# VCO.net
KiCad netlist of a schematic drawn in Altium Designer
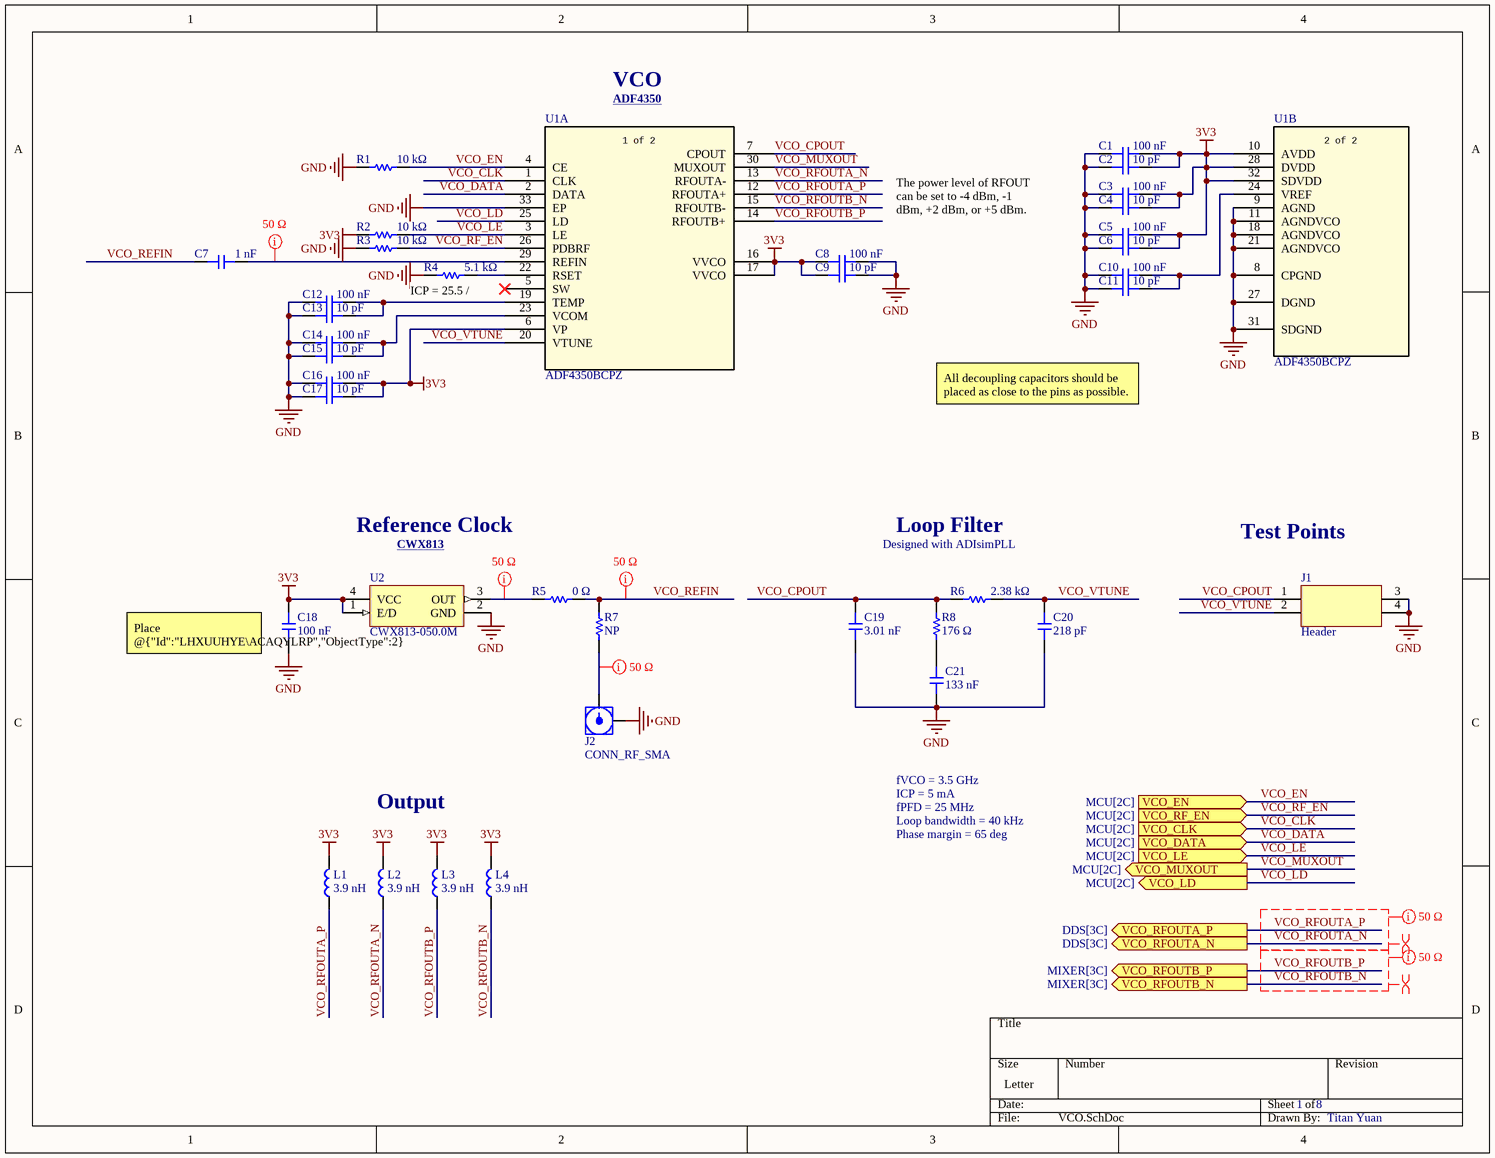
[diagram p0: VCO.SchDoc]

(export (version "E")
  (design (tool "Eeschema 10.0.6"))
  (components
    (comp (ref "C1")
      (value "100 nF")
      (footprint "CAP_0402")
      (description "Ceramic Capacitor, Ceramic, 50V, 10% +Tol, 10% -Tol, X7R, 15% TC, 0.1uF, Surface Mount, 0402")
      (fields
        (field (name "MANUFACTURER") "Yageo")
        (field (name "MANUFACTURER PART NUMBER") "CC0402KPX7R9BB104")
      )
      (libsource (lib "Titan") (part "CAP"))
    )
    (comp (ref "C2")
      (value "10 pF")
      (footprint "CAP_0402")
      (description "50V 10pF C0G ±1% 0402 Multilayer Ceramic Capacitors MLCC - SMD/SMT ROHS")
      (fields
        (field (name "MANUFACTURER") "Murata Electronics")
        (field (name "MANUFACTURER PART NUMBER") "GRM1555C1H100FA01D")
      )
      (libsource (lib "Titan") (part "CAP"))
    )
    (comp (ref "C3")
      (value "100 nF")
      (footprint "CAP_0402")
      (description "Ceramic Capacitor, Ceramic, 50V, 10% +Tol, 10% -Tol, X7R, 15% TC, 0.1uF, Surface Mount, 0402")
      (fields
        (field (name "MANUFACTURER") "Yageo")
        (field (name "MANUFACTURER PART NUMBER") "CC0402KPX7R9BB104")
      )
      (libsource (lib "Titan") (part "CAP"))
    )
    (comp (ref "C4")
      (value "10 pF")
      (footprint "CAP_0402")
      (description "50V 10pF C0G ±1% 0402 Multilayer Ceramic Capacitors MLCC - SMD/SMT ROHS")
      (fields
        (field (name "MANUFACTURER") "Murata Electronics")
        (field (name "MANUFACTURER PART NUMBER") "GRM1555C1H100FA01D")
      )
      (libsource (lib "Titan") (part "CAP"))
    )
    (comp (ref "C5")
      (value "100 nF")
      (footprint "CAP_0402")
      (description "Ceramic Capacitor, Ceramic, 50V, 10% +Tol, 10% -Tol, X7R, 15% TC, 0.1uF, Surface Mount, 0402")
      (fields
        (field (name "MANUFACTURER") "Yageo")
        (field (name "MANUFACTURER PART NUMBER") "CC0402KPX7R9BB104")
      )
      (libsource (lib "Titan") (part "CAP"))
    )
    (comp (ref "C6")
      (value "10 pF")
      (footprint "CAP_0402")
      (description "50V 10pF C0G ±1% 0402 Multilayer Ceramic Capacitors MLCC - SMD/SMT ROHS")
      (fields
        (field (name "MANUFACTURER") "Murata Electronics")
        (field (name "MANUFACTURER PART NUMBER") "GRM1555C1H100FA01D")
      )
      (libsource (lib "Titan") (part "CAP"))
    )
    (comp (ref "C7")
      (value "1 nF")
      (footprint "CAP_0402")
      (description "50V 1nF X7R ±10% 0402 Multilayer Ceramic Capacitors MLCC - SMD/SMT ROHS")
      (fields
        (field (name "MANUFACTURER") "Yageo")
        (field (name "MANUFACTURER PART NUMBER") "CC0402KRX7R9BB102")
      )
      (libsource (lib "Titan") (part "CAP"))
    )
    (comp (ref "C8")
      (value "100 nF")
      (footprint "CAP_0402")
      (description "Ceramic Capacitor, Ceramic, 50V, 10% +Tol, 10% -Tol, X7R, 15% TC, 0.1uF, Surface Mount, 0402")
      (fields
        (field (name "MANUFACTURER") "Yageo")
        (field (name "MANUFACTURER PART NUMBER") "CC0402KPX7R9BB104")
      )
      (libsource (lib "Titan") (part "CAP"))
    )
    (comp (ref "C9")
      (value "10 pF")
      (footprint "CAP_0402")
      (description "50V 10pF C0G ±1% 0402 Multilayer Ceramic Capacitors MLCC - SMD/SMT ROHS")
      (fields
        (field (name "MANUFACTURER") "Murata Electronics")
        (field (name "MANUFACTURER PART NUMBER") "GRM1555C1H100FA01D")
      )
      (libsource (lib "Titan") (part "CAP"))
    )
    (comp (ref "C10")
      (value "100 nF")
      (footprint "CAP_0402")
      (description "Ceramic Capacitor, Ceramic, 50V, 10% +Tol, 10% -Tol, X7R, 15% TC, 0.1uF, Surface Mount, 0402")
      (fields
        (field (name "MANUFACTURER") "Yageo")
        (field (name "MANUFACTURER PART NUMBER") "CC0402KPX7R9BB104")
      )
      (libsource (lib "Titan") (part "CAP"))
    )
    (comp (ref "C11")
      (value "10 pF")
      (footprint "CAP_0402")
      (description "50V 10pF C0G ±1% 0402 Multilayer Ceramic Capacitors MLCC - SMD/SMT ROHS")
      (fields
        (field (name "MANUFACTURER") "Murata Electronics")
        (field (name "MANUFACTURER PART NUMBER") "GRM1555C1H100FA01D")
      )
      (libsource (lib "Titan") (part "CAP"))
    )
    (comp (ref "C12")
      (value "100 nF")
      (footprint "CAP_0402")
      (description "Ceramic Capacitor, Ceramic, 50V, 10% +Tol, 10% -Tol, X7R, 15% TC, 0.1uF, Surface Mount, 0402")
      (fields
        (field (name "MANUFACTURER") "Yageo")
        (field (name "MANUFACTURER PART NUMBER") "CC0402KPX7R9BB104")
      )
      (libsource (lib "Titan") (part "CAP"))
    )
    (comp (ref "C13")
      (value "10 pF")
      (footprint "CAP_0402")
      (description "50V 10pF C0G ±1% 0402 Multilayer Ceramic Capacitors MLCC - SMD/SMT ROHS")
      (fields
        (field (name "MANUFACTURER") "Murata Electronics")
        (field (name "MANUFACTURER PART NUMBER") "GRM1555C1H100FA01D")
      )
      (libsource (lib "Titan") (part "CAP"))
    )
    (comp (ref "C14")
      (value "100 nF")
      (footprint "CAP_0402")
      (description "Ceramic Capacitor, Ceramic, 50V, 10% +Tol, 10% -Tol, X7R, 15% TC, 0.1uF, Surface Mount, 0402")
      (fields
        (field (name "MANUFACTURER") "Yageo")
        (field (name "MANUFACTURER PART NUMBER") "CC0402KPX7R9BB104")
      )
      (libsource (lib "Titan") (part "CAP"))
    )
    (comp (ref "C15")
      (value "10 pF")
      (footprint "CAP_0402")
      (description "50V 10pF C0G ±1% 0402 Multilayer Ceramic Capacitors MLCC - SMD/SMT ROHS")
      (fields
        (field (name "MANUFACTURER") "Murata Electronics")
        (field (name "MANUFACTURER PART NUMBER") "GRM1555C1H100FA01D")
      )
      (libsource (lib "Titan") (part "CAP"))
    )
    (comp (ref "C16")
      (value "100 nF")
      (footprint "CAP_0402")
      (description "Ceramic Capacitor, Ceramic, 50V, 10% +Tol, 10% -Tol, X7R, 15% TC, 0.1uF, Surface Mount, 0402")
      (fields
        (field (name "MANUFACTURER") "Yageo")
        (field (name "MANUFACTURER PART NUMBER") "CC0402KPX7R9BB104")
      )
      (libsource (lib "Titan") (part "CAP"))
    )
    (comp (ref "C17")
      (value "10 pF")
      (footprint "CAP_0402")
      (description "50V 10pF C0G ±1% 0402 Multilayer Ceramic Capacitors MLCC - SMD/SMT ROHS")
      (fields
        (field (name "MANUFACTURER") "Murata Electronics")
        (field (name "MANUFACTURER PART NUMBER") "GRM1555C1H100FA01D")
      )
      (libsource (lib "Titan") (part "CAP"))
    )
    (comp (ref "C18")
      (value "100 nF")
      (footprint "CAP_0402")
      (description "Ceramic Capacitor, Ceramic, 50V, 10% +Tol, 10% -Tol, X7R, 15% TC, 0.1uF, Surface Mount, 0402")
      (fields
        (field (name "MANUFACTURER") "Yageo")
        (field (name "MANUFACTURER PART NUMBER") "CC0402KPX7R9BB104")
      )
      (libsource (lib "Titan") (part "CAP"))
    )
    (comp (ref "C19")
      (value "3.01 nF")
      (footprint "CAP_0603")
      (fields
        (field (name "MANUFACTURER") "Murata Electronics")
        (field (name "MANUFACTURER PART NUMBER") "GCM1885C1H302FA16J")
        (field (name "TOLERANCE") "+-1%")
      )
      (libsource (lib "Titan") (part "CAP"))
    )
    (comp (ref "C20")
      (value "218 pF")
      (footprint "CAP_0603")
      (description "100V 220pF C0G ±1% 0603 Multilayer Ceramic Capacitors MLCC - SMD/SMT ROHS")
      (fields
        (field (name "MANUFACTURER") "Murata Electronics")
        (field (name "MANUFACTURER PART NUMBER") "GCM1885C2A221FA16D")
      )
      (libsource (lib "Titan") (part "CAP"))
    )
    (comp (ref "C21")
      (value "133 nF")
      (footprint "CAP_0603")
      (description "Ceramic Capacitor, Ceramic, 50V, 5% +Tol, 5% -Tol, X7R, 15% TC, 0.15uF, Surface Mount, 0603")
      (fields
        (field (name "MANUFACTURER") "Yageo")
        (field (name "MANUFACTURER PART NUMBER") "CC0603JRX7R9BB154")
      )
      (libsource (lib "Titan") (part "CAP"))
    )
    (comp (ref "J1")
      (value "Header")
      (footprint "CONN_2x2_2.54mm_PinHeader_Vertical")
      (description "Pin Header, Board-to-Board, 2.54 mm, 2 Rows, 4 Contacts, Through Hole, TSW Series")
      (fields
        (field (name "MANUFACTURER") "Samtec")
        (field (name "MANUFACTURER PART NUMBER") "TSW-102-07-F-D")
      )
      (libsource (lib "Titan") (part "CONN_2x2_2.54mm_PinHeader_Vertical"))
    )
    (comp (ref "J2")
      (value "CONN_RF_SMA")
      (footprint "142-0701-801")
      (description "RF / Coaxial Connector, SMA Coaxial, Straight Jack, Solder, 50 ohm, Beryllium Copper")
      (fields
        (field (name "MANUFACTURER") "Cinch Connectivity Solutions Johnson")
        (field (name "MANUFACTURER PART NUMBER") "142-0701-801")
      )
      (libsource (lib "Titan") (part "CONN_RF_SMA"))
    )
    (comp (ref "L1")
      (value "3.9 nH")
      (footprint "IND_0402")
      (description "Inductor RF Chip Wirewound 3.9nH 0.1nH 100MHz 25Q-Factor 750mA 70mOhm DCR 0402 Paper T/R")
      (fields
        (field (name "MANUFACTURER") "Murata Electronics")
        (field (name "MANUFACTURER PART NUMBER") "LQW15AN3N9B00D")
      )
      (libsource (lib "Titan") (part "IND"))
    )
    (comp (ref "L2")
      (value "3.9 nH")
      (footprint "IND_0402")
      (description "Inductor RF Chip Wirewound 3.9nH 0.1nH 100MHz 25Q-Factor 750mA 70mOhm DCR 0402 Paper T/R")
      (fields
        (field (name "MANUFACTURER") "Murata Electronics")
        (field (name "MANUFACTURER PART NUMBER") "LQW15AN3N9B00D")
      )
      (libsource (lib "Titan") (part "IND"))
    )
    (comp (ref "L3")
      (value "3.9 nH")
      (footprint "IND_0402")
      (description "Inductor RF Chip Wirewound 3.9nH 0.1nH 100MHz 25Q-Factor 750mA 70mOhm DCR 0402 Paper T/R")
      (fields
        (field (name "MANUFACTURER") "Murata Electronics")
        (field (name "MANUFACTURER PART NUMBER") "LQW15AN3N9B00D")
      )
      (libsource (lib "Titan") (part "IND"))
    )
    (comp (ref "L4")
      (value "3.9 nH")
      (footprint "IND_0402")
      (description "Inductor RF Chip Wirewound 3.9nH 0.1nH 100MHz 25Q-Factor 750mA 70mOhm DCR 0402 Paper T/R")
      (fields
        (field (name "MANUFACTURER") "Murata Electronics")
        (field (name "MANUFACTURER PART NUMBER") "LQW15AN3N9B00D")
      )
      (libsource (lib "Titan") (part "IND"))
    )
    (comp (ref "R1")
      (value "10 kΩ")
      (footprint "RES_0402")
      (description "Res Thick Film 0402 10K Ohm 1% 0.063W(1/16W) ±100ppm/C Pad SMD T/R")
      (fields
        (field (name "MANUFACTURER") "Yageo")
        (field (name "MANUFACTURER PART NUMBER") "RC0402FR-0710KL")
      )
      (libsource (lib "Titan") (part "RES"))
    )
    (comp (ref "R2")
      (value "10 kΩ")
      (footprint "RES_0402")
      (description "Res Thick Film 0402 10K Ohm 1% 0.063W(1/16W) ±100ppm/C Pad SMD T/R")
      (fields
        (field (name "MANUFACTURER") "Yageo")
        (field (name "MANUFACTURER PART NUMBER") "RC0402FR-0710KL")
      )
      (libsource (lib "Titan") (part "RES"))
    )
    (comp (ref "R3")
      (value "10 kΩ")
      (footprint "RES_0402")
      (description "Res Thick Film 0402 10K Ohm 1% 0.063W(1/16W) ±100ppm/C Pad SMD T/R")
      (fields
        (field (name "MANUFACTURER") "Yageo")
        (field (name "MANUFACTURER PART NUMBER") "RC0402FR-0710KL")
      )
      (libsource (lib "Titan") (part "RES"))
    )
    (comp (ref "R4")
      (value "5.1 kΩ")
      (footprint "RES_0402")
      (description "62.5mW Thick Film Resistors 50V ±100ppm/℃ ±1% 5.1kΩ 0402 Chip Resistor - Surface Mount ROHS")
      (fields
        (field (name "MANUFACTURER") "Yageo")
        (field (name "MANUFACTURER PART NUMBER") "RC0402FR-075K1L")
      )
      (libsource (lib "Titan") (part "RES"))
    )
    (comp (ref "R5")
      (value "0 Ω")
      (footprint "RES_0402")
      (description "GENERAL PURPOSE CHIP RESISTOR Metal Glaze/thick Film, 0.0625W, 0ohm, Surface Mount, 0402")
      (fields
        (field (name "MANUFACTURER") "Yageo")
        (field (name "MANUFACTURER PART NUMBER") "RC0402FR-070RL")
      )
      (libsource (lib "Titan") (part "RES"))
    )
    (comp (ref "R6")
      (value "2.38 kΩ")
      (footprint "RES_0603")
      (description "100mW Thin Film Resistor ±25ppm/℃ ±0.1% 2.37kΩ 0603 Chip Resistor - Surface Mount ROHS")
      (fields
        (field (name "MANUFACTURER") "Yageo")
        (field (name "MANUFACTURER PART NUMBER") "RT0603BRD072K37L")
      )
      (libsource (lib "Titan") (part "RES"))
    )
    (comp (ref "R7")
      (value "NP")
      (footprint "RES_0402")
      (description "Resistor SMD Generic")
      (libsource (lib "Titan") (part "RES"))
    )
    (comp (ref "R8")
      (value "176 Ω")
      (footprint "RES_0603")
      (description "Fixed Resistor, Thin Film, 0.1W, 174ohm, 75V, 0.1% +/-Tol, 25ppm/Cel, Surface Mount, 0603")
      (fields
        (field (name "MANUFACTURER") "Yageo")
        (field (name "MANUFACTURER PART NUMBER") "RT0603BRD07174RL")
      )
      (libsource (lib "Titan") (part "RES"))
    )
    (comp (ref "U1")
      (value "ADF4350BCPZ")
      (footprint "CP_32_2_ADI")
      (description "Clock Generator/Frequency Synthesizer /PLL")
      (fields
        (field (name "MANUFACTURER") "Analog Devices")
        (field (name "COPYRIGHT") "Copyright (C) 2026 Ultra Librarian. All rights reserved.")
      )
      (libsource (lib "ADF4350BCPZ") (part "ADF4350BCPZ"))
    )
    (comp (ref "U2")
      (value "CWX813-050.0M")
      (footprint "CWX8XX")
      (description "LVCMOS Output Clock Oscillator, 50MHz Nom")
      (fields (field (name "MANUFACTURER") "Connor-Winfield"))
      (libsource (lib "Titan") (part "CWX813-050.0M"))
    )
  )
  (nets
    (net (code "1") (name "/VCO_CLK") (class "Default")
      (node (ref "U1") (pin "1") (pinfunction "CLK_1") (pintype "passive"))
    )
    (net (code "2") (name "/VCO_CPOUT") (class "Default")
      (node (ref "C19") (pin "2") (pintype "passive"))
      (node (ref "J1") (pin "1") (pintype "passive"))
      (node (ref "R6") (pin "1") (pintype "passive"))
      (node (ref "R8") (pin "2") (pintype "passive"))
      (node (ref "U1") (pin "7") (pinfunction "CPOUT_7") (pintype "passive"))
    )
    (net (code "3") (name "/VCO_DATA") (class "Default")
      (node (ref "U1") (pin "2") (pinfunction "DATA_2") (pintype "passive"))
    )
    (net (code "4") (name "/VCO_EN") (class "Default")
      (node (ref "R1") (pin "2") (pintype "passive"))
      (node (ref "U1") (pin "4") (pinfunction "CE_4") (pintype "passive"))
    )
    (net (code "5") (name "/VCO_LD") (class "Default")
      (node (ref "U1") (pin "25") (pinfunction "LD_25") (pintype "passive"))
    )
    (net (code "6") (name "/VCO_LE") (class "Default")
      (node (ref "R2") (pin "2") (pintype "passive"))
      (node (ref "U1") (pin "3") (pinfunction "LE_3") (pintype "passive"))
    )
    (net (code "7") (name "/VCO_MUXOUT") (class "Default")
      (node (ref "U1") (pin "30") (pinfunction "MUXOUT_30") (pintype "passive"))
    )
    (net (code "8") (name "/VCO_REFIN") (class "Default")
      (node (ref "C7") (pin "2") (pintype "passive"))
      (node (ref "R5") (pin "2") (pintype "passive"))
      (node (ref "R7") (pin "2") (pintype "passive"))
    )
    (net (code "9") (name "/VCO_RFOUTA_N") (class "Default")
      (node (ref "L2") (pin "1") (pintype "passive"))
      (node (ref "U1") (pin "13") (pinfunction "RFOUTA-_13") (pintype "passive"))
    )
    (net (code "10") (name "/VCO_RFOUTA_P") (class "Default")
      (node (ref "L1") (pin "1") (pintype "passive"))
      (node (ref "U1") (pin "12") (pinfunction "RFOUTA+_12") (pintype "passive"))
    )
    (net (code "11") (name "/VCO_RFOUTB_N") (class "Default")
      (node (ref "L4") (pin "1") (pintype "passive"))
      (node (ref "U1") (pin "15") (pinfunction "RFOUTB-_15") (pintype "passive"))
    )
    (net (code "12") (name "/VCO_RFOUTB_P") (class "Default")
      (node (ref "L3") (pin "1") (pintype "passive"))
      (node (ref "U1") (pin "14") (pinfunction "RFOUTB+_14") (pintype "passive"))
    )
    (net (code "13") (name "/VCO_RF_EN") (class "Default")
      (node (ref "R3") (pin "2") (pintype "passive"))
      (node (ref "U1") (pin "26") (pinfunction "PDBRF_26") (pintype "passive"))
    )
    (net (code "14") (name "/VCO_VTUNE") (class "Default")
      (node (ref "C20") (pin "1") (pintype "passive"))
      (node (ref "J1") (pin "2") (pintype "passive"))
      (node (ref "R6") (pin "2") (pintype "passive"))
      (node (ref "U1") (pin "20") (pinfunction "VTUNE_20") (pintype "passive"))
    )
    (net (code "15") (name "3V3") (class "Default")
      (node (ref "C1") (pin "2") (pintype "passive"))
      (node (ref "C16") (pin "2") (pintype "passive"))
      (node (ref "C17") (pin "2") (pintype "passive"))
      (node (ref "C18") (pin "2") (pintype "passive"))
      (node (ref "C2") (pin "2") (pintype "passive"))
      (node (ref "C3") (pin "2") (pintype "passive"))
      (node (ref "C4") (pin "2") (pintype "passive"))
      (node (ref "C5") (pin "2") (pintype "passive"))
      (node (ref "C6") (pin "2") (pintype "passive"))
      (node (ref "C8") (pin "1") (pintype "passive"))
      (node (ref "C9") (pin "1") (pintype "passive"))
      (node (ref "L1") (pin "2") (pintype "passive"))
      (node (ref "L2") (pin "2") (pintype "passive"))
      (node (ref "L3") (pin "2") (pintype "passive"))
      (node (ref "L4") (pin "2") (pintype "passive"))
      (node (ref "R2") (pin "1") (pintype "passive"))
      (node (ref "U1") (pin "10") (pinfunction "AVDD_10") (pintype "passive"))
      (node (ref "U1") (pin "16") (pinfunction "VVCO_16") (pintype "passive"))
      (node (ref "U1") (pin "17") (pinfunction "VVCO_17") (pintype "passive"))
      (node (ref "U1") (pin "28") (pinfunction "DVDD_28") (pintype "passive"))
      (node (ref "U1") (pin "32") (pinfunction "SDVDD_32") (pintype "passive"))
      (node (ref "U1") (pin "6") (pinfunction "VP_6") (pintype "passive"))
      (node (ref "U2") (pin "1") (pinfunction "E/D_1") (pintype "input"))
      (node (ref "U2") (pin "4") (pinfunction "VCC_4") (pintype "power_in"))
    )
    (net (code "16") (name "GND") (class "Default")
      (node (ref "C1") (pin "1") (pintype "passive"))
      (node (ref "C10") (pin "1") (pintype "passive"))
      (node (ref "C11") (pin "1") (pintype "passive"))
      (node (ref "C12") (pin "1") (pintype "passive"))
      (node (ref "C13") (pin "1") (pintype "passive"))
      (node (ref "C14") (pin "1") (pintype "passive"))
      (node (ref "C15") (pin "1") (pintype "passive"))
      (node (ref "C16") (pin "1") (pintype "passive"))
      (node (ref "C17") (pin "1") (pintype "passive"))
      (node (ref "C18") (pin "1") (pintype "passive"))
      (node (ref "C19") (pin "1") (pintype "passive"))
      (node (ref "C2") (pin "1") (pintype "passive"))
      (node (ref "C20") (pin "2") (pintype "passive"))
      (node (ref "C21") (pin "1") (pintype "passive"))
      (node (ref "C3") (pin "1") (pintype "passive"))
      (node (ref "C4") (pin "1") (pintype "passive"))
      (node (ref "C5") (pin "1") (pintype "passive"))
      (node (ref "C6") (pin "1") (pintype "passive"))
      (node (ref "C8") (pin "2") (pintype "passive"))
      (node (ref "C9") (pin "2") (pintype "passive"))
      (node (ref "J1") (pin "3") (pintype "passive"))
      (node (ref "J1") (pin "4") (pintype "passive"))
      (node (ref "J2") (pin "2") (pintype "passive"))
      (node (ref "R1") (pin "1") (pintype "passive"))
      (node (ref "R3") (pin "1") (pintype "passive"))
      (node (ref "R4") (pin "2") (pintype "passive"))
      (node (ref "U1") (pin "11") (pinfunction "AGNDVCO_11") (pintype "passive"))
      (node (ref "U1") (pin "18") (pinfunction "AGNDVCO_18") (pintype "passive"))
      (node (ref "U1") (pin "21") (pinfunction "AGNDVCO_21") (pintype "passive"))
      (node (ref "U1") (pin "27") (pinfunction "DGND_27") (pintype "passive"))
      (node (ref "U1") (pin "31") (pinfunction "SDGND_31") (pintype "passive"))
      (node (ref "U1") (pin "33") (pinfunction "EP_33") (pintype "passive"))
      (node (ref "U1") (pin "8") (pinfunction "CPGND_8") (pintype "passive"))
      (node (ref "U1") (pin "9") (pinfunction "AGND_9") (pintype "passive"))
      (node (ref "U2") (pin "2") (pinfunction "GND_2") (pintype "power_in"))
    )
    (net (code "17") (name "Net-(C21-Pad2)") (class "Default")
      (node (ref "C21") (pin "2") (pintype "passive"))
      (node (ref "R8") (pin "1") (pintype "passive"))
    )
    (net (code "18") (name "Net-(J2-Pad1)") (class "Default")
      (node (ref "J2") (pin "1") (pintype "passive"))
      (node (ref "R7") (pin "1") (pintype "passive"))
    )
    (net (code "19") (name "Net-(U1A-REFIN)") (class "Default")
      (node (ref "C7") (pin "1") (pintype "passive"))
      (node (ref "U1") (pin "29") (pinfunction "REFIN_29") (pintype "passive"))
    )
    (net (code "20") (name "Net-(U1A-RSET)") (class "Default")
      (node (ref "R4") (pin "1") (pintype "passive"))
      (node (ref "U1") (pin "22") (pinfunction "RSET_22") (pintype "passive"))
    )
    (net (code "21") (name "Net-(U1A-TEMP)") (class "Default")
      (node (ref "C12") (pin "2") (pintype "passive"))
      (node (ref "C13") (pin "2") (pintype "passive"))
      (node (ref "U1") (pin "19") (pinfunction "TEMP_19") (pintype "passive"))
    )
    (net (code "22") (name "Net-(U1A-VCOM)") (class "Default")
      (node (ref "C14") (pin "2") (pintype "passive"))
      (node (ref "C15") (pin "2") (pintype "passive"))
      (node (ref "U1") (pin "23") (pinfunction "VCOM_23") (pintype "passive"))
    )
    (net (code "23") (name "Net-(U1B-VREF)") (class "Default")
      (node (ref "C10") (pin "2") (pintype "passive"))
      (node (ref "C11") (pin "2") (pintype "passive"))
      (node (ref "U1") (pin "24") (pinfunction "VREF_24") (pintype "passive"))
    )
    (net (code "24") (name "Net-(U2-OUT)") (class "Default")
      (node (ref "R5") (pin "1") (pintype "passive"))
      (node (ref "U2") (pin "3") (pinfunction "OUT_3") (pintype "output"))
    )
    (net (code "25") (name "unconnected-(U1A-SW-Pad5)") (class "Default")
      (node (ref "U1") (pin "5") (pinfunction "SW_5") (pintype "passive+no_connect"))
    )
  )
)
